# robot_main_board.net
KiCad netlist of a schematic drawn in EAGLE
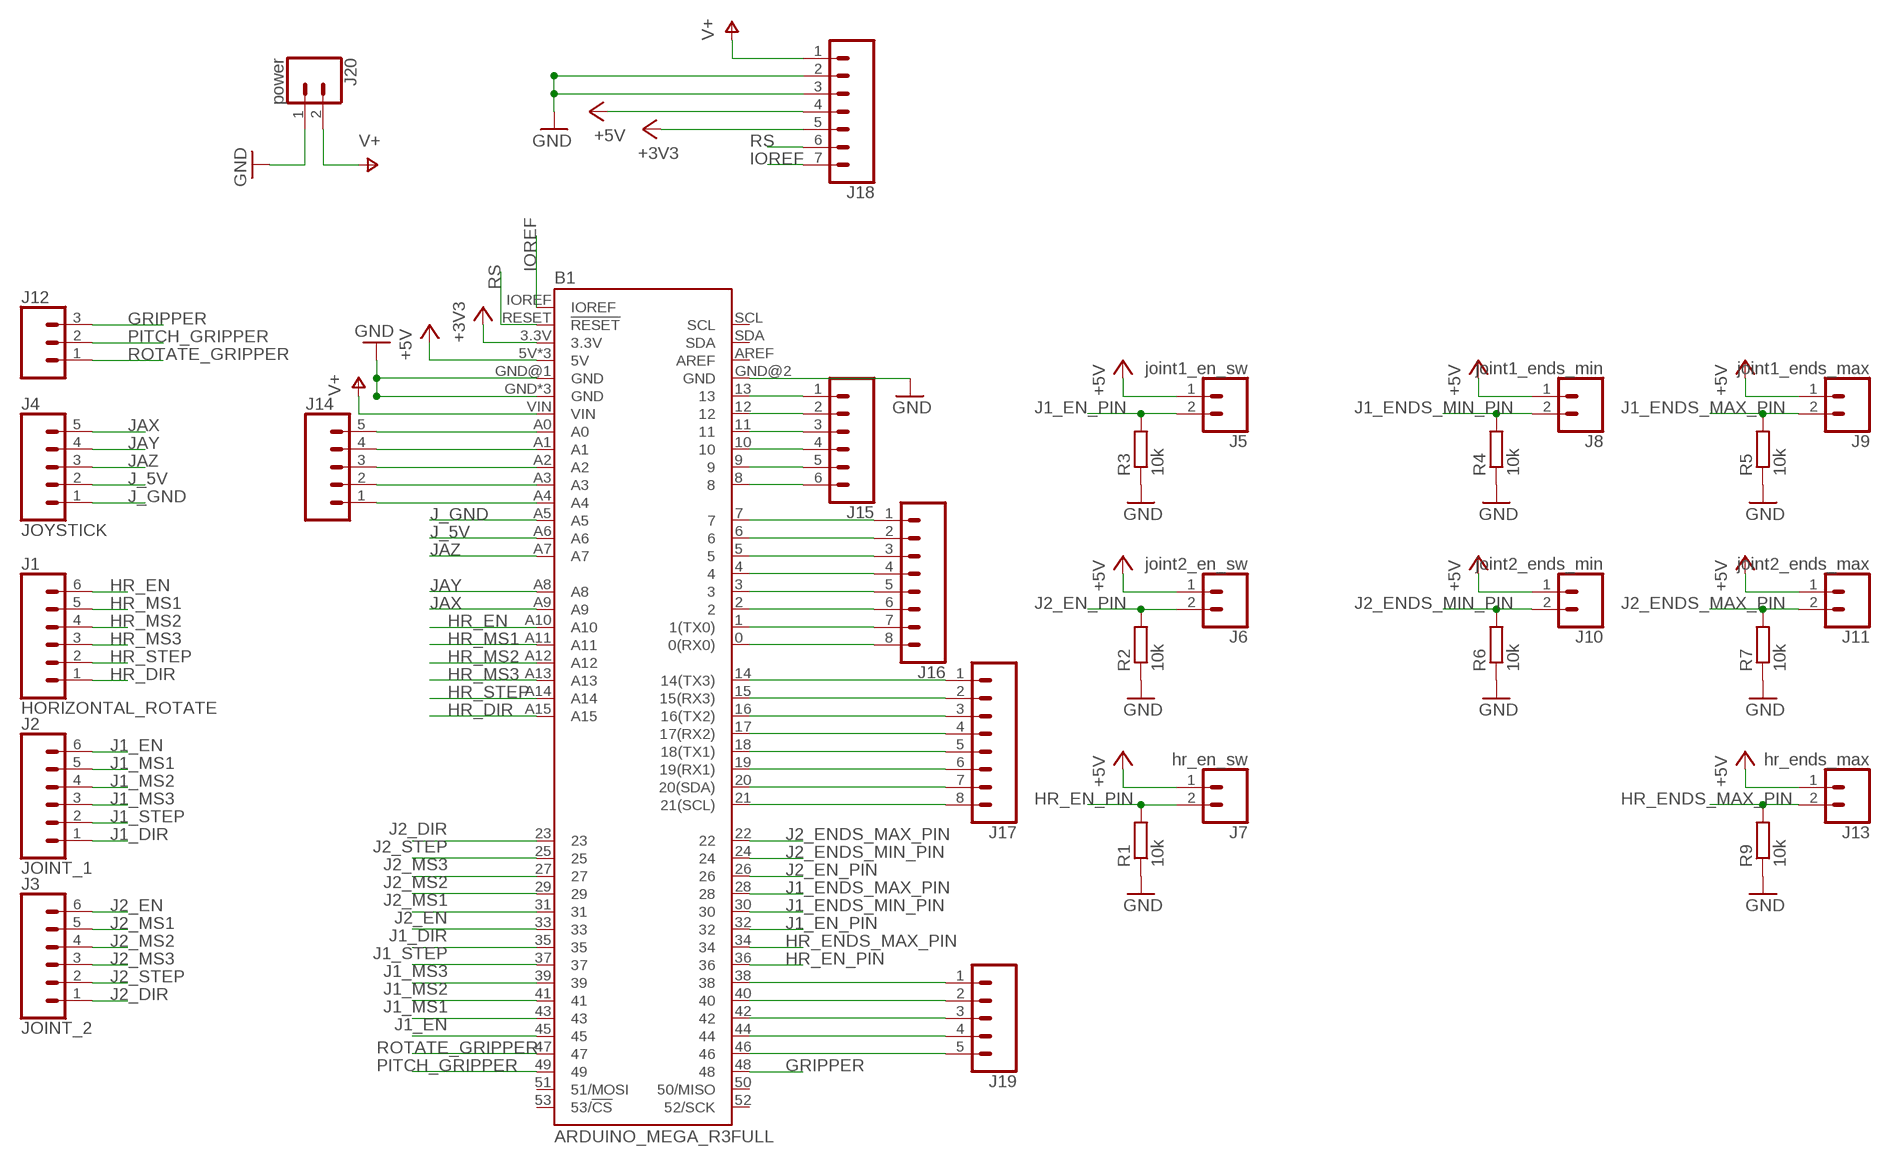
[diagram p0: schematic, sheet 1]

(export (version "E")
  (design (tool "Eeschema 10.0.6"))
  (components
    (comp (ref "B1")
      (value "ARDUINO_MEGA_R3FULL")
      (footprint "eagle-import:ARDUINO_MEGA_NO_SILK")
      (libsource (lib "eagle-import") (part "ARDUINO_MEGA_R3FULL"))
    )
    (comp (ref "J1")
      (value "HORIZONTAL_ROTATE")
      (footprint "eagle-import:MOLEX-1X6")
      (libsource (lib "eagle-import") (part "CONN_06POLAR"))
    )
    (comp (ref "J2")
      (value "JOINT_1")
      (footprint "eagle-import:MOLEX-1X6")
      (libsource (lib "eagle-import") (part "CONN_06POLAR"))
    )
    (comp (ref "J3")
      (value "JOINT_2")
      (footprint "eagle-import:MOLEX-1X6")
      (libsource (lib "eagle-import") (part "CONN_06POLAR"))
    )
    (comp (ref "J4")
      (value "JOYSTICK")
      (footprint "eagle-import:1X05")
      (libsource (lib "eagle-import") (part "CONN_05"))
    )
    (comp (ref "J5")
      (value "joint1_en_sw")
      (footprint "eagle-import:MOLEX-1X2")
      (libsource (lib "eagle-import") (part "CONN_02POLAR"))
    )
    (comp (ref "J6")
      (value "joint2_en_sw")
      (footprint "eagle-import:MOLEX-1X2")
      (libsource (lib "eagle-import") (part "CONN_02POLAR"))
    )
    (comp (ref "J7")
      (value "hr_en_sw")
      (footprint "eagle-import:MOLEX-1X2")
      (libsource (lib "eagle-import") (part "CONN_02POLAR"))
    )
    (comp (ref "J8")
      (value "joint1_ends_min")
      (footprint "eagle-import:MOLEX-1X2")
      (libsource (lib "eagle-import") (part "CONN_02POLAR"))
    )
    (comp (ref "J9")
      (value "joint1_ends_max")
      (footprint "eagle-import:MOLEX-1X2")
      (libsource (lib "eagle-import") (part "CONN_02POLAR"))
    )
    (comp (ref "J10")
      (value "joint2_ends_min")
      (footprint "eagle-import:MOLEX-1X2")
      (libsource (lib "eagle-import") (part "CONN_02POLAR"))
    )
    (comp (ref "J11")
      (value "joint2_ends_max")
      (footprint "eagle-import:MOLEX-1X2")
      (libsource (lib "eagle-import") (part "CONN_02POLAR"))
    )
    (comp (ref "J12")
      (value "CONN_03POLAR")
      (footprint "eagle-import:MOLEX-1X3")
      (libsource (lib "eagle-import") (part "CONN_03POLAR"))
    )
    (comp (ref "J13")
      (value "hr_ends_max")
      (footprint "eagle-import:MOLEX-1X2")
      (libsource (lib "eagle-import") (part "CONN_02POLAR"))
    )
    (comp (ref "J14")
      (value "CONN_05")
      (footprint "eagle-import:1X05")
      (libsource (lib "eagle-import") (part "CONN_05"))
    )
    (comp (ref "J15")
      (value "CONN_06SILK_FEMALE_PTH")
      (footprint "eagle-import:1X06")
      (libsource (lib "eagle-import") (part "CONN_06SILK_FEMALE_PTH"))
    )
    (comp (ref "J16")
      (value "CONN_08\"")
      (footprint "eagle-import:1X08")
      (libsource (lib "eagle-import") (part "CONN_08{dblquote}"))
    )
    (comp (ref "J17")
      (value "CONN_08\"")
      (footprint "eagle-import:1X08")
      (libsource (lib "eagle-import") (part "CONN_08{dblquote}"))
    )
    (comp (ref "J18")
      (value "CONN_07")
      (footprint "eagle-import:1X07")
      (libsource (lib "eagle-import") (part "CONN_07"))
    )
    (comp (ref "J19")
      (value "CONN_05")
      (footprint "eagle-import:1X05")
      (libsource (lib "eagle-import") (part "CONN_05"))
    )
    (comp (ref "J20")
      (value "power")
      (footprint "eagle-import:MOLEX-1X2")
      (libsource (lib "eagle-import") (part "CONN_02POLAR"))
    )
    (comp (ref "R1")
      (value "10k")
      (footprint "eagle-import:0204_7")
      (libsource (lib "eagle-import") (part "R-EU_0204/7"))
    )
    (comp (ref "R2")
      (value "10k")
      (footprint "eagle-import:0204_7")
      (libsource (lib "eagle-import") (part "R-EU_0204/7"))
    )
    (comp (ref "R3")
      (value "10k")
      (footprint "eagle-import:0204_7")
      (libsource (lib "eagle-import") (part "R-EU_0204/7"))
    )
    (comp (ref "R4")
      (value "10k")
      (footprint "eagle-import:0204_7")
      (libsource (lib "eagle-import") (part "R-EU_0204/7"))
    )
    (comp (ref "R5")
      (value "10k")
      (footprint "eagle-import:0204_7")
      (libsource (lib "eagle-import") (part "R-EU_0204/7"))
    )
    (comp (ref "R6")
      (value "10k")
      (footprint "eagle-import:0204_7")
      (libsource (lib "eagle-import") (part "R-EU_0204/7"))
    )
    (comp (ref "R7")
      (value "10k")
      (footprint "eagle-import:0204_7")
      (libsource (lib "eagle-import") (part "R-EU_0204/7"))
    )
    (comp (ref "R9")
      (value "10k")
      (footprint "eagle-import:0204_7")
      (libsource (lib "eagle-import") (part "R-EU_0204/7"))
    )
  )
  (nets
    (net (code "1") (name "+3V3") (class "Default")
      (node (ref "B1") (pin "3.3V") (pinfunction "3.3V_3.3V") (pintype "bidirectional"))
      (node (ref "J18") (pin "5") (pinfunction "5_5") (pintype "passive"))
    )
    (net (code "2") (name "+5V") (class "Default")
      (node (ref "B1") (pin "5V") (pinfunction "5V_5V") (pintype "bidirectional"))
      (node (ref "B1") (pin "5V@1") (pinfunction "5V_5V@1") (pintype "bidirectional"))
      (node (ref "B1") (pin "5V@2") (pinfunction "5V_5V@2") (pintype "bidirectional"))
      (node (ref "J10") (pin "1") (pinfunction "1_1") (pintype "passive"))
      (node (ref "J11") (pin "1") (pinfunction "1_1") (pintype "passive"))
      (node (ref "J13") (pin "1") (pinfunction "1_1") (pintype "passive"))
      (node (ref "J18") (pin "4") (pinfunction "4_4") (pintype "passive"))
      (node (ref "J5") (pin "1") (pinfunction "1_1") (pintype "passive"))
      (node (ref "J6") (pin "1") (pinfunction "1_1") (pintype "passive"))
      (node (ref "J7") (pin "1") (pinfunction "1_1") (pintype "passive"))
      (node (ref "J8") (pin "1") (pinfunction "1_1") (pintype "passive"))
      (node (ref "J9") (pin "1") (pinfunction "1_1") (pintype "passive"))
    )
    (net (code "3") (name "/GRIPPER") (class "Default")
      (node (ref "B1") (pin "48") (pinfunction "48_48") (pintype "bidirectional"))
      (node (ref "J12") (pin "3") (pinfunction "3_3") (pintype "passive"))
    )
    (net (code "4") (name "/HR_DIR") (class "Default")
      (node (ref "B1") (pin "A15") (pinfunction "A15_A15") (pintype "bidirectional"))
      (node (ref "J1") (pin "1") (pinfunction "1_1") (pintype "passive"))
    )
    (net (code "5") (name "/HR_EN") (class "Default")
      (node (ref "B1") (pin "A10") (pinfunction "A10_A10") (pintype "bidirectional"))
      (node (ref "J1") (pin "6") (pinfunction "6_6") (pintype "passive"))
    )
    (net (code "6") (name "/HR_ENDS_MAX_PIN") (class "Default")
      (node (ref "B1") (pin "34") (pinfunction "34_34") (pintype "bidirectional"))
      (node (ref "J13") (pin "2") (pinfunction "2_2") (pintype "passive"))
      (node (ref "R9") (pin "2") (pinfunction "2_2") (pintype "passive"))
    )
    (net (code "7") (name "/HR_EN_PIN") (class "Default")
      (node (ref "B1") (pin "36") (pinfunction "36_36") (pintype "bidirectional"))
      (node (ref "J7") (pin "2") (pinfunction "2_2") (pintype "passive"))
      (node (ref "R1") (pin "2") (pinfunction "2_2") (pintype "passive"))
    )
    (net (code "8") (name "/HR_MS1") (class "Default")
      (node (ref "B1") (pin "A11") (pinfunction "A11_A11") (pintype "bidirectional"))
      (node (ref "J1") (pin "5") (pinfunction "5_5") (pintype "passive"))
    )
    (net (code "9") (name "/HR_MS2") (class "Default")
      (node (ref "B1") (pin "A12") (pinfunction "A12_A12") (pintype "bidirectional"))
      (node (ref "J1") (pin "4") (pinfunction "4_4") (pintype "passive"))
    )
    (net (code "10") (name "/HR_MS3") (class "Default")
      (node (ref "B1") (pin "A13") (pinfunction "A13_A13") (pintype "bidirectional"))
      (node (ref "J1") (pin "3") (pinfunction "3_3") (pintype "passive"))
    )
    (net (code "11") (name "/HR_STEP") (class "Default")
      (node (ref "B1") (pin "A14") (pinfunction "A14_A14") (pintype "bidirectional"))
      (node (ref "J1") (pin "2") (pinfunction "2_2") (pintype "passive"))
    )
    (net (code "12") (name "/IOREF") (class "Default")
      (node (ref "B1") (pin "IOREF") (pinfunction "IOREF_IOREF") (pintype "bidirectional"))
      (node (ref "J18") (pin "7") (pinfunction "7_7") (pintype "passive"))
    )
    (net (code "13") (name "/J1_DIR") (class "Default")
      (node (ref "B1") (pin "35") (pinfunction "35_35") (pintype "bidirectional"))
      (node (ref "J2") (pin "1") (pinfunction "1_1") (pintype "passive"))
    )
    (net (code "14") (name "/J1_EN") (class "Default")
      (node (ref "B1") (pin "45") (pinfunction "45_45") (pintype "bidirectional"))
      (node (ref "J2") (pin "6") (pinfunction "6_6") (pintype "passive"))
    )
    (net (code "15") (name "/J1_ENDS_MAX_PIN") (class "Default")
      (node (ref "B1") (pin "28") (pinfunction "28_28") (pintype "bidirectional"))
      (node (ref "J9") (pin "2") (pinfunction "2_2") (pintype "passive"))
      (node (ref "R5") (pin "2") (pinfunction "2_2") (pintype "passive"))
    )
    (net (code "16") (name "/J1_ENDS_MIN_PIN") (class "Default")
      (node (ref "B1") (pin "30") (pinfunction "30_30") (pintype "bidirectional"))
      (node (ref "J8") (pin "2") (pinfunction "2_2") (pintype "passive"))
      (node (ref "R4") (pin "2") (pinfunction "2_2") (pintype "passive"))
    )
    (net (code "17") (name "/J1_EN_PIN") (class "Default")
      (node (ref "B1") (pin "32") (pinfunction "32_32") (pintype "bidirectional"))
      (node (ref "J5") (pin "2") (pinfunction "2_2") (pintype "passive"))
      (node (ref "R3") (pin "2") (pinfunction "2_2") (pintype "passive"))
    )
    (net (code "18") (name "/J1_MS1") (class "Default")
      (node (ref "B1") (pin "43") (pinfunction "43_43") (pintype "bidirectional"))
      (node (ref "J2") (pin "5") (pinfunction "5_5") (pintype "passive"))
    )
    (net (code "19") (name "/J1_MS2") (class "Default")
      (node (ref "B1") (pin "41") (pinfunction "41_41") (pintype "bidirectional"))
      (node (ref "J2") (pin "4") (pinfunction "4_4") (pintype "passive"))
    )
    (net (code "20") (name "/J1_MS3") (class "Default")
      (node (ref "B1") (pin "39") (pinfunction "39_39") (pintype "bidirectional"))
      (node (ref "J2") (pin "3") (pinfunction "3_3") (pintype "passive"))
    )
    (net (code "21") (name "/J1_STEP") (class "Default")
      (node (ref "B1") (pin "37") (pinfunction "37_37") (pintype "bidirectional"))
      (node (ref "J2") (pin "2") (pinfunction "2_2") (pintype "passive"))
    )
    (net (code "22") (name "/J2_DIR") (class "Default")
      (node (ref "B1") (pin "23") (pinfunction "23_23") (pintype "bidirectional"))
      (node (ref "J3") (pin "1") (pinfunction "1_1") (pintype "passive"))
    )
    (net (code "23") (name "/J2_EN") (class "Default")
      (node (ref "B1") (pin "33") (pinfunction "33_33") (pintype "bidirectional"))
      (node (ref "J3") (pin "6") (pinfunction "6_6") (pintype "passive"))
    )
    (net (code "24") (name "/J2_ENDS_MAX_PIN") (class "Default")
      (node (ref "B1") (pin "22") (pinfunction "22_22") (pintype "bidirectional"))
      (node (ref "J11") (pin "2") (pinfunction "2_2") (pintype "passive"))
      (node (ref "R7") (pin "2") (pinfunction "2_2") (pintype "passive"))
    )
    (net (code "25") (name "/J2_ENDS_MIN_PIN") (class "Default")
      (node (ref "B1") (pin "24") (pinfunction "24_24") (pintype "bidirectional"))
      (node (ref "J10") (pin "2") (pinfunction "2_2") (pintype "passive"))
      (node (ref "R6") (pin "2") (pinfunction "2_2") (pintype "passive"))
    )
    (net (code "26") (name "/J2_EN_PIN") (class "Default")
      (node (ref "B1") (pin "26") (pinfunction "26_26") (pintype "bidirectional"))
      (node (ref "J6") (pin "2") (pinfunction "2_2") (pintype "passive"))
      (node (ref "R2") (pin "2") (pinfunction "2_2") (pintype "passive"))
    )
    (net (code "27") (name "/J2_MS1") (class "Default")
      (node (ref "B1") (pin "31") (pinfunction "31_31") (pintype "bidirectional"))
      (node (ref "J3") (pin "5") (pinfunction "5_5") (pintype "passive"))
    )
    (net (code "28") (name "/J2_MS2") (class "Default")
      (node (ref "B1") (pin "29") (pinfunction "29_29") (pintype "bidirectional"))
      (node (ref "J3") (pin "4") (pinfunction "4_4") (pintype "passive"))
    )
    (net (code "29") (name "/J2_MS3") (class "Default")
      (node (ref "B1") (pin "27") (pinfunction "27_27") (pintype "bidirectional"))
      (node (ref "J3") (pin "3") (pinfunction "3_3") (pintype "passive"))
    )
    (net (code "30") (name "/J2_STEP") (class "Default")
      (node (ref "B1") (pin "25") (pinfunction "25_25") (pintype "bidirectional"))
      (node (ref "J3") (pin "2") (pinfunction "2_2") (pintype "passive"))
    )
    (net (code "31") (name "/JAX") (class "Default")
      (node (ref "B1") (pin "A9") (pinfunction "A9_A9") (pintype "bidirectional"))
      (node (ref "J4") (pin "5") (pinfunction "5_5") (pintype "passive"))
    )
    (net (code "32") (name "/JAY") (class "Default")
      (node (ref "B1") (pin "A8") (pinfunction "A8_A8") (pintype "bidirectional"))
      (node (ref "J4") (pin "4") (pinfunction "4_4") (pintype "passive"))
    )
    (net (code "33") (name "/JAZ") (class "Default")
      (node (ref "B1") (pin "A7") (pinfunction "A7_A7") (pintype "bidirectional"))
      (node (ref "J4") (pin "3") (pinfunction "3_3") (pintype "passive"))
    )
    (net (code "34") (name "/J_5V") (class "Default")
      (node (ref "B1") (pin "A6") (pinfunction "A6_A6") (pintype "bidirectional"))
      (node (ref "J4") (pin "2") (pinfunction "2_2") (pintype "passive"))
    )
    (net (code "35") (name "/J_GND") (class "Default")
      (node (ref "B1") (pin "A5") (pinfunction "A5_A5") (pintype "bidirectional"))
      (node (ref "J4") (pin "1") (pinfunction "1_1") (pintype "passive"))
    )
    (net (code "36") (name "/PITCH_GRIPPER") (class "Default")
      (node (ref "B1") (pin "49") (pinfunction "49_49") (pintype "bidirectional"))
      (node (ref "J12") (pin "2") (pinfunction "2_2") (pintype "passive"))
    )
    (net (code "37") (name "/ROTATE_GRIPPER") (class "Default")
      (node (ref "B1") (pin "47") (pinfunction "47_47") (pintype "bidirectional"))
      (node (ref "J12") (pin "1") (pinfunction "1_1") (pintype "passive"))
    )
    (net (code "38") (name "/RS") (class "Default")
      (node (ref "B1") (pin "RESET") (pinfunction "~{RESET}_RESET") (pintype "bidirectional"))
      (node (ref "J18") (pin "6") (pinfunction "6_6") (pintype "passive"))
    )
    (net (code "39") (name "GND") (class "Default")
      (node (ref "B1") (pin "GND") (pinfunction "GND_GND") (pintype "bidirectional"))
      (node (ref "B1") (pin "GND@1") (pinfunction "GND_GND@1") (pintype "bidirectional"))
      (node (ref "B1") (pin "GND@2") (pinfunction "GND_GND@2") (pintype "bidirectional"))
      (node (ref "B1") (pin "GND@3") (pinfunction "GND_GND@3") (pintype "bidirectional"))
      (node (ref "B1") (pin "GND@4") (pinfunction "GND_GND@4") (pintype "bidirectional"))
      (node (ref "J18") (pin "2") (pinfunction "2_2") (pintype "passive"))
      (node (ref "J18") (pin "3") (pinfunction "3_3") (pintype "passive"))
      (node (ref "J20") (pin "1") (pinfunction "1_1") (pintype "passive"))
      (node (ref "R1") (pin "1") (pinfunction "1_1") (pintype "passive"))
      (node (ref "R2") (pin "1") (pinfunction "1_1") (pintype "passive"))
      (node (ref "R3") (pin "1") (pinfunction "1_1") (pintype "passive"))
      (node (ref "R4") (pin "1") (pinfunction "1_1") (pintype "passive"))
      (node (ref "R5") (pin "1") (pinfunction "1_1") (pintype "passive"))
      (node (ref "R6") (pin "1") (pinfunction "1_1") (pintype "passive"))
      (node (ref "R7") (pin "1") (pinfunction "1_1") (pintype "passive"))
      (node (ref "R9") (pin "1") (pinfunction "1_1") (pintype "passive"))
    )
    (net (code "40") (name "Net-(B1-0(RX0))") (class "Default")
      (node (ref "B1") (pin "0") (pinfunction "0(RX0)_0") (pintype "bidirectional"))
      (node (ref "J16") (pin "8") (pinfunction "8_8") (pintype "passive"))
    )
    (net (code "41") (name "Net-(B1-1(TX0))") (class "Default")
      (node (ref "B1") (pin "1") (pinfunction "1(TX0)_1") (pintype "bidirectional"))
      (node (ref "J16") (pin "7") (pinfunction "7_7") (pintype "passive"))
    )
    (net (code "42") (name "Net-(B1-14(TX3))") (class "Default")
      (node (ref "B1") (pin "14") (pinfunction "14(TX3)_14") (pintype "bidirectional"))
      (node (ref "J17") (pin "1") (pinfunction "1_1") (pintype "passive"))
    )
    (net (code "43") (name "Net-(B1-15(RX3))") (class "Default")
      (node (ref "B1") (pin "15") (pinfunction "15(RX3)_15") (pintype "bidirectional"))
      (node (ref "J17") (pin "2") (pinfunction "2_2") (pintype "passive"))
    )
    (net (code "44") (name "Net-(B1-16(TX2))") (class "Default")
      (node (ref "B1") (pin "16") (pinfunction "16(TX2)_16") (pintype "bidirectional"))
      (node (ref "J17") (pin "3") (pinfunction "3_3") (pintype "passive"))
    )
    (net (code "45") (name "Net-(B1-17(RX2))") (class "Default")
      (node (ref "B1") (pin "17") (pinfunction "17(RX2)_17") (pintype "bidirectional"))
      (node (ref "J17") (pin "4") (pinfunction "4_4") (pintype "passive"))
    )
    (net (code "46") (name "Net-(B1-18(TX1))") (class "Default")
      (node (ref "B1") (pin "18") (pinfunction "18(TX1)_18") (pintype "bidirectional"))
      (node (ref "J17") (pin "5") (pinfunction "5_5") (pintype "passive"))
    )
    (net (code "47") (name "Net-(B1-19(RX1))") (class "Default")
      (node (ref "B1") (pin "19") (pinfunction "19(RX1)_19") (pintype "bidirectional"))
      (node (ref "J17") (pin "6") (pinfunction "6_6") (pintype "passive"))
    )
    (net (code "48") (name "Net-(B1-20(SDA))") (class "Default")
      (node (ref "B1") (pin "20") (pinfunction "20(SDA)_20") (pintype "bidirectional"))
      (node (ref "J17") (pin "7") (pinfunction "7_7") (pintype "passive"))
    )
    (net (code "49") (name "Net-(B1-21(SCL))") (class "Default")
      (node (ref "B1") (pin "21") (pinfunction "21(SCL)_21") (pintype "bidirectional"))
      (node (ref "J17") (pin "8") (pinfunction "8_8") (pintype "passive"))
    )
    (net (code "50") (name "Net-(B1-Pad2)") (class "Default")
      (node (ref "B1") (pin "2") (pinfunction "2_2") (pintype "bidirectional"))
      (node (ref "J16") (pin "6") (pinfunction "6_6") (pintype "passive"))
    )
    (net (code "51") (name "Net-(B1-Pad3)") (class "Default")
      (node (ref "B1") (pin "3") (pinfunction "3_3") (pintype "bidirectional"))
      (node (ref "J16") (pin "5") (pinfunction "5_5") (pintype "passive"))
    )
    (net (code "52") (name "Net-(B1-Pad4)") (class "Default")
      (node (ref "B1") (pin "4") (pinfunction "4_4") (pintype "bidirectional"))
      (node (ref "J16") (pin "4") (pinfunction "4_4") (pintype "passive"))
    )
    (net (code "53") (name "Net-(B1-Pad5)") (class "Default")
      (node (ref "B1") (pin "5") (pinfunction "5_5") (pintype "bidirectional"))
      (node (ref "J16") (pin "3") (pinfunction "3_3") (pintype "passive"))
    )
    (net (code "54") (name "Net-(B1-Pad6)") (class "Default")
      (node (ref "B1") (pin "6") (pinfunction "6_6") (pintype "bidirectional"))
      (node (ref "J16") (pin "2") (pinfunction "2_2") (pintype "passive"))
    )
    (net (code "55") (name "Net-(B1-Pad7)") (class "Default")
      (node (ref "B1") (pin "7") (pinfunction "7_7") (pintype "bidirectional"))
      (node (ref "J16") (pin "1") (pinfunction "1_1") (pintype "passive"))
    )
    (net (code "56") (name "Net-(B1-Pad8)") (class "Default")
      (node (ref "B1") (pin "8") (pinfunction "8_8") (pintype "bidirectional"))
      (node (ref "J15") (pin "6") (pinfunction "6_6") (pintype "passive"))
    )
    (net (code "57") (name "Net-(B1-Pad9)") (class "Default")
      (node (ref "B1") (pin "9") (pinfunction "9_9") (pintype "bidirectional"))
      (node (ref "J15") (pin "5") (pinfunction "5_5") (pintype "passive"))
    )
    (net (code "58") (name "Net-(B1-Pad10)") (class "Default")
      (node (ref "B1") (pin "10") (pinfunction "10_10") (pintype "bidirectional"))
      (node (ref "J15") (pin "4") (pinfunction "4_4") (pintype "passive"))
    )
    (net (code "59") (name "Net-(B1-Pad11)") (class "Default")
      (node (ref "B1") (pin "11") (pinfunction "11_11") (pintype "bidirectional"))
      (node (ref "J15") (pin "3") (pinfunction "3_3") (pintype "passive"))
    )
    (net (code "60") (name "Net-(B1-Pad12)") (class "Default")
      (node (ref "B1") (pin "12") (pinfunction "12_12") (pintype "bidirectional"))
      (node (ref "J15") (pin "2") (pinfunction "2_2") (pintype "passive"))
    )
    (net (code "61") (name "Net-(B1-Pad13)") (class "Default")
      (node (ref "B1") (pin "13") (pinfunction "13_13") (pintype "bidirectional"))
      (node (ref "J15") (pin "1") (pinfunction "1_1") (pintype "passive"))
    )
    (net (code "62") (name "Net-(B1-Pad38)") (class "Default")
      (node (ref "B1") (pin "38") (pinfunction "38_38") (pintype "bidirectional"))
      (node (ref "J19") (pin "1") (pinfunction "1_1") (pintype "passive"))
    )
    (net (code "63") (name "Net-(B1-Pad40)") (class "Default")
      (node (ref "B1") (pin "40") (pinfunction "40_40") (pintype "bidirectional"))
      (node (ref "J19") (pin "2") (pinfunction "2_2") (pintype "passive"))
    )
    (net (code "64") (name "Net-(B1-Pad42)") (class "Default")
      (node (ref "B1") (pin "42") (pinfunction "42_42") (pintype "bidirectional"))
      (node (ref "J19") (pin "3") (pinfunction "3_3") (pintype "passive"))
    )
    (net (code "65") (name "Net-(B1-Pad44)") (class "Default")
      (node (ref "B1") (pin "44") (pinfunction "44_44") (pintype "bidirectional"))
      (node (ref "J19") (pin "4") (pinfunction "4_4") (pintype "passive"))
    )
    (net (code "66") (name "Net-(B1-Pad46)") (class "Default")
      (node (ref "B1") (pin "46") (pinfunction "46_46") (pintype "bidirectional"))
      (node (ref "J19") (pin "5") (pinfunction "5_5") (pintype "passive"))
    )
    (net (code "67") (name "Net-(B1-PadA0)") (class "Default")
      (node (ref "B1") (pin "A0") (pinfunction "A0_A0") (pintype "bidirectional"))
      (node (ref "J14") (pin "5") (pinfunction "5_5") (pintype "passive"))
    )
    (net (code "68") (name "Net-(B1-PadA1)") (class "Default")
      (node (ref "B1") (pin "A1") (pinfunction "A1_A1") (pintype "bidirectional"))
      (node (ref "J14") (pin "4") (pinfunction "4_4") (pintype "passive"))
    )
    (net (code "69") (name "Net-(B1-PadA2)") (class "Default")
      (node (ref "B1") (pin "A2") (pinfunction "A2_A2") (pintype "bidirectional"))
      (node (ref "J14") (pin "3") (pinfunction "3_3") (pintype "passive"))
    )
    (net (code "70") (name "Net-(B1-PadA3)") (class "Default")
      (node (ref "B1") (pin "A3") (pinfunction "A3_A3") (pintype "bidirectional"))
      (node (ref "J14") (pin "2") (pinfunction "2_2") (pintype "passive"))
    )
    (net (code "71") (name "Net-(B1-PadA4)") (class "Default")
      (node (ref "B1") (pin "A4") (pinfunction "A4_A4") (pintype "bidirectional"))
      (node (ref "J14") (pin "1") (pinfunction "1_1") (pintype "passive"))
    )
    (net (code "72") (name "V+") (class "Default")
      (node (ref "B1") (pin "VIN") (pinfunction "VIN_VIN") (pintype "bidirectional"))
      (node (ref "J18") (pin "1") (pinfunction "1_1") (pintype "passive"))
      (node (ref "J20") (pin "2") (pinfunction "2_2") (pintype "passive"))
    )
    (net (code "73") (name "unconnected-(B1-50{slash}MISO-Pad50)") (class "Default")
      (node (ref "B1") (pin "50") (pinfunction "50/MISO_50") (pintype "bidirectional"))
    )
    (net (code "74") (name "unconnected-(B1-51{slash}MOSI-Pad51)") (class "Default")
      (node (ref "B1") (pin "51") (pinfunction "51/MOSI_51") (pintype "bidirectional"))
    )
    (net (code "75") (name "unconnected-(B1-52{slash}SCK-Pad52)") (class "Default")
      (node (ref "B1") (pin "52") (pinfunction "52/SCK_52") (pintype "bidirectional"))
    )
    (net (code "76") (name "unconnected-(B1-53{slash}~{CS}-Pad53)") (class "Default")
      (node (ref "B1") (pin "53") (pinfunction "53/~{CS}_53") (pintype "bidirectional"))
    )
    (net (code "77") (name "unconnected-(B1-PadAREF)") (class "Default")
      (node (ref "B1") (pin "AREF") (pinfunction "AREF_AREF") (pintype "bidirectional"))
    )
    (net (code "78") (name "unconnected-(B1-PadSCL)") (class "Default")
      (node (ref "B1") (pin "SCL") (pinfunction "SCL_SCL") (pintype "bidirectional"))
    )
    (net (code "79") (name "unconnected-(B1-PadSDA)") (class "Default")
      (node (ref "B1") (pin "SDA") (pinfunction "SDA_SDA") (pintype "bidirectional"))
    )
  )
)
